# NewWiring.net
KiCad netlist of a schematic drawn in EAGLE
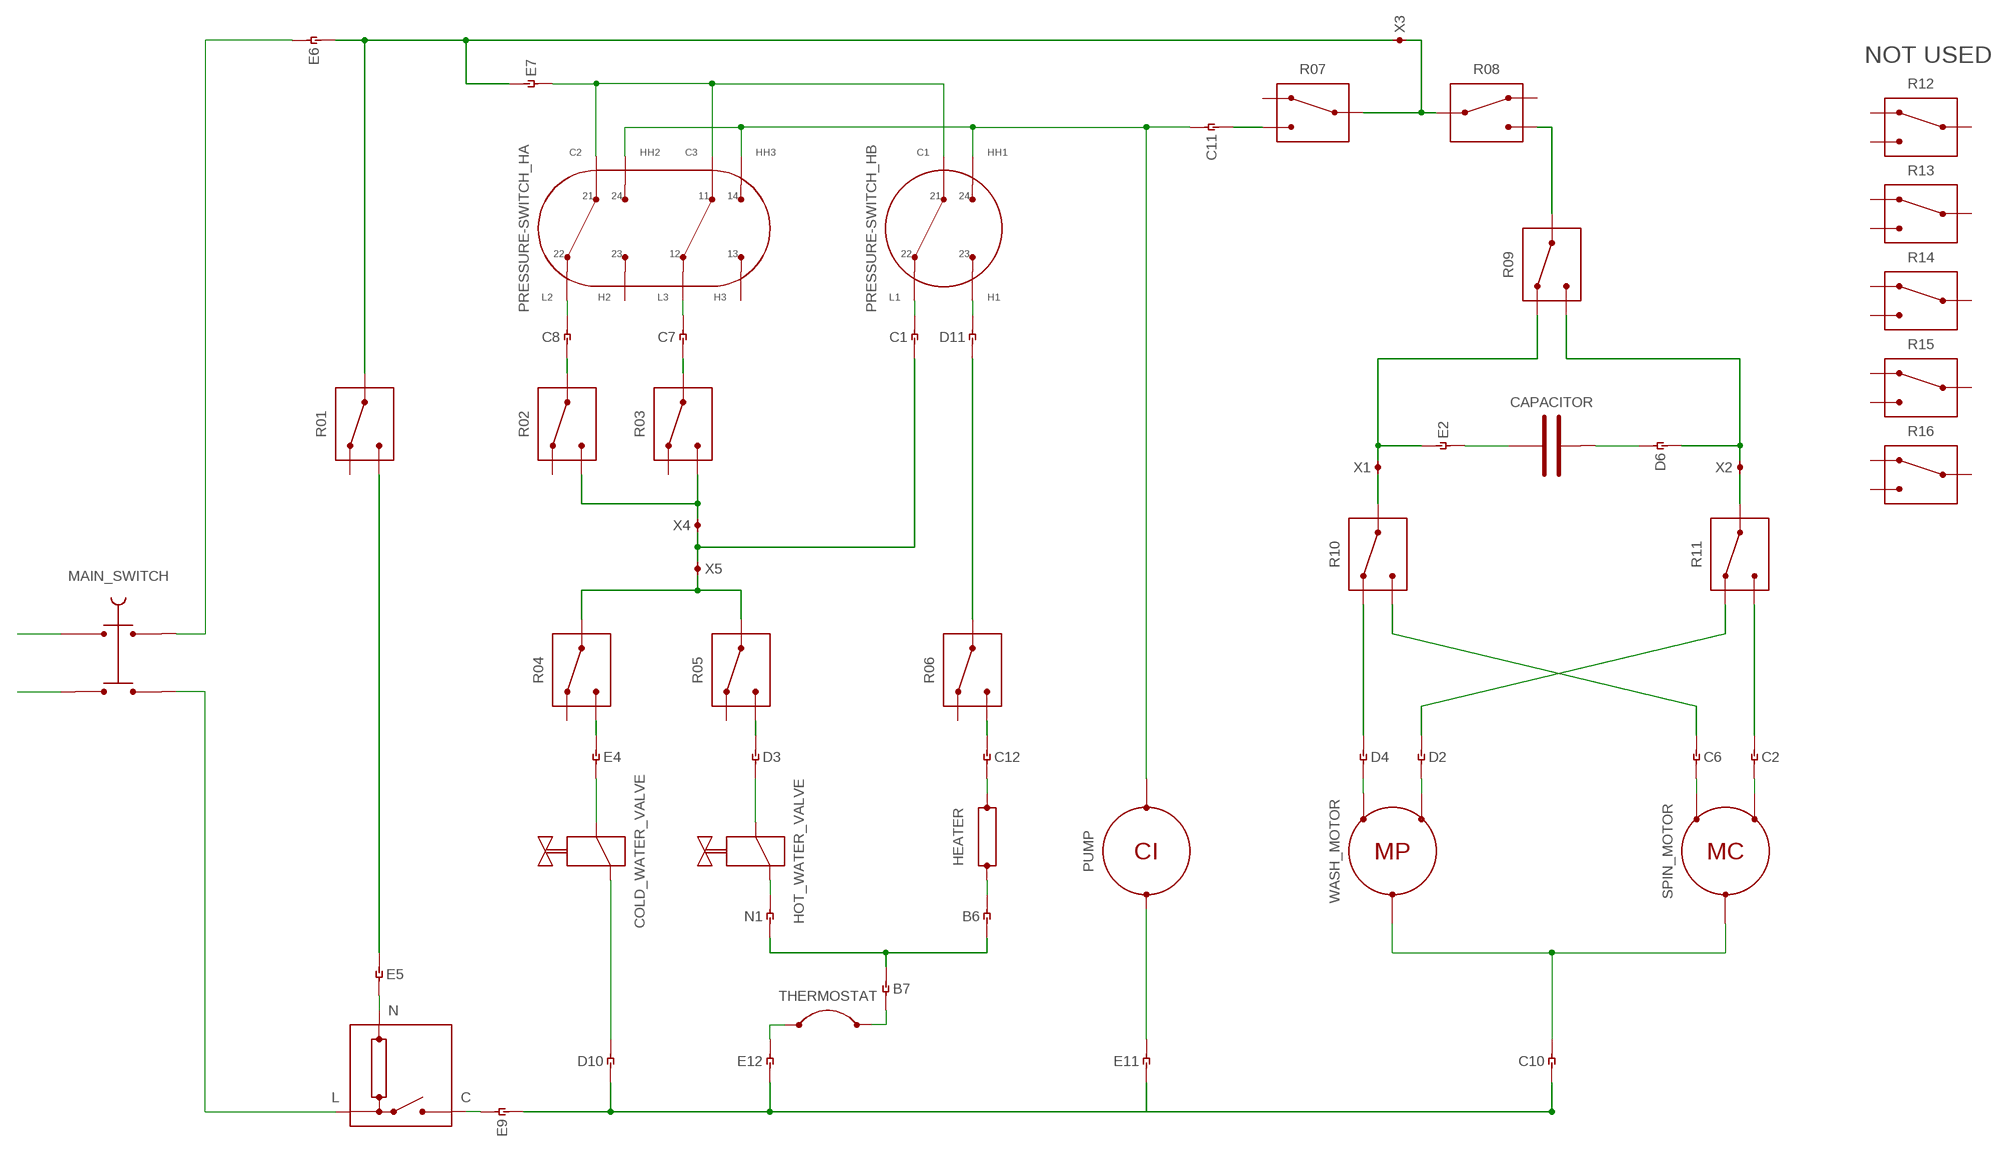
[diagram p0: schematic, sheet 1]

(export (version "E")
  (design (tool "Eeschema 10.0.6"))
  (components
    (comp (ref "B6")
      (value "CABLE")
      (footprint "eagle-import:CABLE")
      (libsource (lib "eagle-import") (part "CABLE"))
    )
    (comp (ref "B7")
      (value "CABLE")
      (footprint "eagle-import:CABLE")
      (libsource (lib "eagle-import") (part "CABLE"))
    )
    (comp (ref "C1")
      (value "CABLE")
      (footprint "eagle-import:CABLE")
      (libsource (lib "eagle-import") (part "CABLE"))
    )
    (comp (ref "C2")
      (value "CABLE")
      (footprint "eagle-import:CABLE")
      (libsource (lib "eagle-import") (part "CABLE"))
    )
    (comp (ref "C6")
      (value "CABLE")
      (footprint "eagle-import:CABLE")
      (libsource (lib "eagle-import") (part "CABLE"))
    )
    (comp (ref "C7")
      (value "CABLE")
      (footprint "eagle-import:CABLE")
      (libsource (lib "eagle-import") (part "CABLE"))
    )
    (comp (ref "C8")
      (value "CABLE")
      (footprint "eagle-import:CABLE")
      (libsource (lib "eagle-import") (part "CABLE"))
    )
    (comp (ref "C10")
      (value "CABLE")
      (footprint "eagle-import:CABLE")
      (libsource (lib "eagle-import") (part "CABLE"))
    )
    (comp (ref "C11")
      (value "CABLE")
      (footprint "eagle-import:CABLE")
      (libsource (lib "eagle-import") (part "CABLE"))
    )
    (comp (ref "C12")
      (value "CABLE")
      (footprint "eagle-import:CABLE")
      (libsource (lib "eagle-import") (part "CABLE"))
    )
    (comp (ref "CAPACITOR")
      (value "CAPACITOR")
      (footprint "eagle-import:CAPACITOR")
      (libsource (lib "eagle-import") (part "CAPACITOR"))
    )
    (comp (ref "COLD_WATER_VALVE")
      (value "VALVE")
      (footprint "eagle-import:VALVE")
      (libsource (lib "eagle-import") (part "VALVE"))
    )
    (comp (ref "D2")
      (value "CABLE")
      (footprint "eagle-import:CABLE")
      (libsource (lib "eagle-import") (part "CABLE"))
    )
    (comp (ref "D3")
      (value "CABLE")
      (footprint "eagle-import:CABLE")
      (libsource (lib "eagle-import") (part "CABLE"))
    )
    (comp (ref "D4")
      (value "CABLE")
      (footprint "eagle-import:CABLE")
      (libsource (lib "eagle-import") (part "CABLE"))
    )
    (comp (ref "D6")
      (value "CABLE")
      (footprint "eagle-import:CABLE")
      (libsource (lib "eagle-import") (part "CABLE"))
    )
    (comp (ref "D10")
      (value "CABLE")
      (footprint "eagle-import:CABLE")
      (libsource (lib "eagle-import") (part "CABLE"))
    )
    (comp (ref "D11")
      (value "CABLE")
      (footprint "eagle-import:CABLE")
      (libsource (lib "eagle-import") (part "CABLE"))
    )
    (comp (ref "E2")
      (value "CABLE")
      (footprint "eagle-import:CABLE")
      (libsource (lib "eagle-import") (part "CABLE"))
    )
    (comp (ref "E4")
      (value "CABLE")
      (footprint "eagle-import:CABLE")
      (libsource (lib "eagle-import") (part "CABLE"))
    )
    (comp (ref "E5")
      (value "CABLE")
      (footprint "eagle-import:CABLE")
      (libsource (lib "eagle-import") (part "CABLE"))
    )
    (comp (ref "E6")
      (value "CABLE")
      (footprint "eagle-import:CABLE")
      (libsource (lib "eagle-import") (part "CABLE"))
    )
    (comp (ref "E7")
      (value "CABLE")
      (footprint "eagle-import:CABLE")
      (libsource (lib "eagle-import") (part "CABLE"))
    )
    (comp (ref "E9")
      (value "CABLE")
      (footprint "eagle-import:CABLE")
      (libsource (lib "eagle-import") (part "CABLE"))
    )
    (comp (ref "E11")
      (value "CABLE")
      (footprint "eagle-import:CABLE")
      (libsource (lib "eagle-import") (part "CABLE"))
    )
    (comp (ref "E12")
      (value "CABLE")
      (footprint "eagle-import:CABLE")
      (libsource (lib "eagle-import") (part "CABLE"))
    )
    (comp (ref "HEATER")
      (value "HEATER")
      (footprint "eagle-import:HEATER")
      (libsource (lib "eagle-import") (part "HEATER"))
    )
    (comp (ref "HOT_WATER_VALVE")
      (value "VALVE")
      (footprint "eagle-import:VALVE")
      (libsource (lib "eagle-import") (part "VALVE"))
    )
    (comp (ref "MAIN_SWITCH")
      (value "SWITCH")
      (footprint "eagle-import:SWITCH")
      (libsource (lib "eagle-import") (part "SWITCH"))
    )
    (comp (ref "N1")
      (value "CABLE")
      (footprint "eagle-import:CABLE")
      (libsource (lib "eagle-import") (part "CABLE"))
    )
    (comp (ref "PRESSURE-SWITCH_HA")
      (value "PS2")
      (footprint "eagle-import:PS2")
      (libsource (lib "eagle-import") (part "PS2"))
    )
    (comp (ref "PRESSURE-SWITCH_HB")
      (value "PS1")
      (footprint "eagle-import:PS1")
      (libsource (lib "eagle-import") (part "PS1"))
    )
    (comp (ref "PUMP")
      (value "CI")
      (footprint "eagle-import:MOTOR-2")
      (libsource (lib "eagle-import") (part "MOTOR-2"))
    )
    (comp (ref "R01")
      (value "RELAY")
      (footprint "eagle-import:RELAY")
      (libsource (lib "eagle-import") (part "RELAY"))
    )
    (comp (ref "R02")
      (value "RELAY")
      (footprint "eagle-import:RELAY")
      (libsource (lib "eagle-import") (part "RELAY"))
    )
    (comp (ref "R03")
      (value "RELAY")
      (footprint "eagle-import:RELAY")
      (libsource (lib "eagle-import") (part "RELAY"))
    )
    (comp (ref "R04")
      (value "RELAY")
      (footprint "eagle-import:RELAY")
      (libsource (lib "eagle-import") (part "RELAY"))
    )
    (comp (ref "R05")
      (value "RELAY")
      (footprint "eagle-import:RELAY")
      (libsource (lib "eagle-import") (part "RELAY"))
    )
    (comp (ref "R06")
      (value "RELAY")
      (footprint "eagle-import:RELAY")
      (libsource (lib "eagle-import") (part "RELAY"))
    )
    (comp (ref "R07")
      (value "RELAY")
      (footprint "eagle-import:RELAY")
      (libsource (lib "eagle-import") (part "RELAY"))
    )
    (comp (ref "R08")
      (value "RELAY")
      (footprint "eagle-import:RELAY")
      (libsource (lib "eagle-import") (part "RELAY"))
    )
    (comp (ref "R09")
      (value "RELAY")
      (footprint "eagle-import:RELAY")
      (libsource (lib "eagle-import") (part "RELAY"))
    )
    (comp (ref "R10")
      (value "RELAY")
      (footprint "eagle-import:RELAY")
      (libsource (lib "eagle-import") (part "RELAY"))
    )
    (comp (ref "R11")
      (value "RELAY")
      (footprint "eagle-import:RELAY")
      (libsource (lib "eagle-import") (part "RELAY"))
    )
    (comp (ref "R12")
      (value "RELAY")
      (footprint "eagle-import:RELAY")
      (libsource (lib "eagle-import") (part "RELAY"))
    )
    (comp (ref "R13")
      (value "RELAY")
      (footprint "eagle-import:RELAY")
      (libsource (lib "eagle-import") (part "RELAY"))
    )
    (comp (ref "R14")
      (value "RELAY")
      (footprint "eagle-import:RELAY")
      (libsource (lib "eagle-import") (part "RELAY"))
    )
    (comp (ref "R15")
      (value "RELAY")
      (footprint "eagle-import:RELAY")
      (libsource (lib "eagle-import") (part "RELAY"))
    )
    (comp (ref "R16")
      (value "RELAY")
      (footprint "eagle-import:RELAY")
      (libsource (lib "eagle-import") (part "RELAY"))
    )
    (comp (ref "SPIN_MOTOR")
      (value "MC")
      (footprint "eagle-import:MOTOR-3")
      (libsource (lib "eagle-import") (part "MOTOR-3"))
    )
    (comp (ref "THERMOSTAT")
      (value "THERMOSTAT")
      (footprint "eagle-import:THERMOSTAT")
      (libsource (lib "eagle-import") (part "THERMOSTAT"))
    )
    (comp (ref "U$1")
      (value "LOCK")
      (footprint "eagle-import:LOCK")
      (libsource (lib "eagle-import") (part "LOCK"))
    )
    (comp (ref "WASH_MOTOR")
      (value "MP")
      (footprint "eagle-import:MOTOR-3")
      (libsource (lib "eagle-import") (part "MOTOR-3"))
    )
    (comp (ref "X1")
      (value "DOMINO")
      (footprint "eagle-import:DOMINO")
      (libsource (lib "eagle-import") (part "DOMINO"))
    )
    (comp (ref "X2")
      (value "DOMINO")
      (footprint "eagle-import:DOMINO")
      (libsource (lib "eagle-import") (part "DOMINO"))
    )
    (comp (ref "X3")
      (value "DOMINO")
      (footprint "eagle-import:DOMINO")
      (libsource (lib "eagle-import") (part "DOMINO"))
    )
    (comp (ref "X4")
      (value "DOMINO")
      (footprint "eagle-import:DOMINO")
      (libsource (lib "eagle-import") (part "DOMINO"))
    )
    (comp (ref "X5")
      (value "DOMINO")
      (footprint "eagle-import:DOMINO")
      (libsource (lib "eagle-import") (part "DOMINO"))
    )
  )
  (nets
    (net (code "1") (name "Net-(B6-PIN1)") (class "Default")
      (node (ref "B6") (pin "P$1") (pinfunction "PIN1_P$1") (pintype "bidirectional"))
      (node (ref "B7") (pin "P$1") (pinfunction "PIN1_P$1") (pintype "bidirectional"))
      (node (ref "N1") (pin "P$1") (pinfunction "PIN1_P$1") (pintype "bidirectional"))
    )
    (net (code "2") (name "Net-(B6-PIN2)") (class "Default")
      (node (ref "B6") (pin "P$2") (pinfunction "PIN2_P$2") (pintype "bidirectional"))
      (node (ref "HEATER") (pin "H1") (pinfunction "P$1_H1") (pintype "bidirectional"))
    )
    (net (code "3") (name "Net-(B7-PIN2)") (class "Default")
      (node (ref "B7") (pin "P$2") (pinfunction "PIN2_P$2") (pintype "bidirectional"))
      (node (ref "THERMOSTAT") (pin "T1") (pinfunction "P$1_T1") (pintype "bidirectional"))
    )
    (net (code "4") (name "Net-(C1-PIN1)") (class "Default")
      (node (ref "C1") (pin "P$1") (pinfunction "PIN1_P$1") (pintype "bidirectional"))
      (node (ref "X4") (pin "P$1") (pinfunction "PIN1_P$1") (pintype "bidirectional"))
      (node (ref "X5") (pin "P$1") (pinfunction "PIN1_P$1") (pintype "bidirectional"))
    )
    (net (code "5") (name "Net-(C1-PIN2)") (class "Default")
      (node (ref "C1") (pin "P$2") (pinfunction "PIN2_P$2") (pintype "bidirectional"))
      (node (ref "PRESSURE-SWITCH_HB") (pin "P$3") (pinfunction "P$3_P$3") (pintype "bidirectional"))
    )
    (net (code "6") (name "Net-(C2-PIN1)") (class "Default")
      (node (ref "C2") (pin "P$1") (pinfunction "PIN1_P$1") (pintype "bidirectional"))
      (node (ref "R11") (pin "T") (pinfunction "T_T") (pintype "bidirectional"))
    )
    (net (code "7") (name "Net-(C2-PIN2)") (class "Default")
      (node (ref "C2") (pin "P$2") (pinfunction "PIN2_P$2") (pintype "bidirectional"))
      (node (ref "SPIN_MOTOR") (pin "M3") (pinfunction "M2_M3") (pintype "bidirectional"))
    )
    (net (code "8") (name "Net-(C6-PIN1)") (class "Default")
      (node (ref "C6") (pin "P$1") (pinfunction "PIN1_P$1") (pintype "bidirectional"))
      (node (ref "R10") (pin "T") (pinfunction "T_T") (pintype "bidirectional"))
    )
    (net (code "9") (name "Net-(C6-PIN2)") (class "Default")
      (node (ref "C6") (pin "P$2") (pinfunction "PIN2_P$2") (pintype "bidirectional"))
      (node (ref "SPIN_MOTOR") (pin "M1") (pinfunction "M1_M1") (pintype "bidirectional"))
    )
    (net (code "10") (name "Net-(C7-PIN1)") (class "Default")
      (node (ref "C7") (pin "P$1") (pinfunction "PIN1_P$1") (pintype "bidirectional"))
      (node (ref "R03") (pin "C") (pinfunction "C_C") (pintype "bidirectional"))
    )
    (net (code "11") (name "Net-(C7-PIN2)") (class "Default")
      (node (ref "C7") (pin "P$2") (pinfunction "PIN2_P$2") (pintype "bidirectional"))
      (node (ref "PRESSURE-SWITCH_HA") (pin "P$6") (pinfunction "P$7_P$6") (pintype "bidirectional"))
    )
    (net (code "12") (name "Net-(C8-PIN1)") (class "Default")
      (node (ref "C8") (pin "P$1") (pinfunction "PIN1_P$1") (pintype "bidirectional"))
      (node (ref "R02") (pin "C") (pinfunction "C_C") (pintype "bidirectional"))
    )
    (net (code "13") (name "Net-(C8-PIN2)") (class "Default")
      (node (ref "C8") (pin "P$2") (pinfunction "PIN2_P$2") (pintype "bidirectional"))
      (node (ref "PRESSURE-SWITCH_HA") (pin "P$2") (pinfunction "P$3_P$2") (pintype "bidirectional"))
    )
    (net (code "14") (name "Net-(C10-PIN1)") (class "Default")
      (node (ref "C10") (pin "P$1") (pinfunction "PIN1_P$1") (pintype "bidirectional"))
      (node (ref "D10") (pin "P$1") (pinfunction "PIN1_P$1") (pintype "bidirectional"))
      (node (ref "E11") (pin "P$1") (pinfunction "PIN1_P$1") (pintype "bidirectional"))
      (node (ref "E12") (pin "P$1") (pinfunction "PIN1_P$1") (pintype "bidirectional"))
      (node (ref "E9") (pin "P$1") (pinfunction "PIN1_P$1") (pintype "bidirectional"))
    )
    (net (code "15") (name "Net-(C10-PIN2)") (class "Default")
      (node (ref "C10") (pin "P$2") (pinfunction "PIN2_P$2") (pintype "bidirectional"))
      (node (ref "SPIN_MOTOR") (pin "MC") (pinfunction "MC_MC") (pintype "bidirectional"))
      (node (ref "WASH_MOTOR") (pin "MC") (pinfunction "MC_MC") (pintype "bidirectional"))
    )
    (net (code "16") (name "Net-(C11-PIN1)") (class "Default")
      (node (ref "C11") (pin "P$1") (pinfunction "PIN1_P$1") (pintype "bidirectional"))
      (node (ref "R07") (pin "T") (pinfunction "T_T") (pintype "bidirectional"))
    )
    (net (code "17") (name "Net-(C11-PIN2)") (class "Default")
      (node (ref "C11") (pin "P$2") (pinfunction "PIN2_P$2") (pintype "bidirectional"))
      (node (ref "PRESSURE-SWITCH_HA") (pin "P$5") (pinfunction "P$6_P$5") (pintype "bidirectional"))
      (node (ref "PRESSURE-SWITCH_HA") (pin "P$8") (pinfunction "P$2_P$8") (pintype "bidirectional"))
      (node (ref "PRESSURE-SWITCH_HB") (pin "P$2") (pinfunction "P$2_P$2") (pintype "bidirectional"))
      (node (ref "PUMP") (pin "M1") (pinfunction "M1_M1") (pintype "bidirectional"))
    )
    (net (code "18") (name "Net-(C12-PIN1)") (class "Default")
      (node (ref "C12") (pin "P$1") (pinfunction "PIN1_P$1") (pintype "bidirectional"))
      (node (ref "R06") (pin "T") (pinfunction "T_T") (pintype "bidirectional"))
    )
    (net (code "19") (name "Net-(C12-PIN2)") (class "Default")
      (node (ref "C12") (pin "P$2") (pinfunction "PIN2_P$2") (pintype "bidirectional"))
      (node (ref "HEATER") (pin "H2") (pinfunction "P$2_H2") (pintype "bidirectional"))
    )
    (net (code "20") (name "Net-(D2-PIN1)") (class "Default")
      (node (ref "D2") (pin "P$1") (pinfunction "PIN1_P$1") (pintype "bidirectional"))
      (node (ref "R11") (pin "R") (pinfunction "R_R") (pintype "bidirectional"))
    )
    (net (code "21") (name "Net-(D2-PIN2)") (class "Default")
      (node (ref "D2") (pin "P$2") (pinfunction "PIN2_P$2") (pintype "bidirectional"))
      (node (ref "WASH_MOTOR") (pin "M3") (pinfunction "M2_M3") (pintype "bidirectional"))
    )
    (net (code "22") (name "Net-(D3-PIN1)") (class "Default")
      (node (ref "D3") (pin "P$1") (pinfunction "PIN1_P$1") (pintype "bidirectional"))
      (node (ref "R05") (pin "T") (pinfunction "T_T") (pintype "bidirectional"))
    )
    (net (code "23") (name "Net-(D3-PIN2)") (class "Default")
      (node (ref "D3") (pin "P$2") (pinfunction "PIN2_P$2") (pintype "bidirectional"))
      (node (ref "HOT_WATER_VALVE") (pin "P$2") (pinfunction "P$2_P$2") (pintype "bidirectional"))
    )
    (net (code "24") (name "Net-(D4-PIN1)") (class "Default")
      (node (ref "D4") (pin "P$1") (pinfunction "PIN1_P$1") (pintype "bidirectional"))
      (node (ref "R10") (pin "R") (pinfunction "R_R") (pintype "bidirectional"))
    )
    (net (code "25") (name "Net-(D4-PIN2)") (class "Default")
      (node (ref "D4") (pin "P$2") (pinfunction "PIN2_P$2") (pintype "bidirectional"))
      (node (ref "WASH_MOTOR") (pin "M1") (pinfunction "M1_M1") (pintype "bidirectional"))
    )
    (net (code "26") (name "Net-(D6-PIN1)") (class "Default")
      (node (ref "D6") (pin "P$1") (pinfunction "PIN1_P$1") (pintype "bidirectional"))
      (node (ref "R09") (pin "T") (pinfunction "T_T") (pintype "bidirectional"))
      (node (ref "X2") (pin "P$2") (pinfunction "PIN2_P$2") (pintype "bidirectional"))
    )
    (net (code "27") (name "Net-(D6-PIN2)") (class "Default")
      (node (ref "CAPACITOR") (pin "C2") (pinfunction "C2_C2") (pintype "bidirectional"))
      (node (ref "D6") (pin "P$2") (pinfunction "PIN2_P$2") (pintype "bidirectional"))
    )
    (net (code "28") (name "Net-(D10-PIN2)") (class "Default")
      (node (ref "COLD_WATER_VALVE") (pin "P$1") (pinfunction "P$1_P$1") (pintype "bidirectional"))
      (node (ref "D10") (pin "P$2") (pinfunction "PIN2_P$2") (pintype "bidirectional"))
    )
    (net (code "29") (name "Net-(D11-PIN1)") (class "Default")
      (node (ref "D11") (pin "P$1") (pinfunction "PIN1_P$1") (pintype "bidirectional"))
      (node (ref "R06") (pin "C") (pinfunction "C_C") (pintype "bidirectional"))
    )
    (net (code "30") (name "Net-(D11-PIN2)") (class "Default")
      (node (ref "D11") (pin "P$2") (pinfunction "PIN2_P$2") (pintype "bidirectional"))
      (node (ref "PRESSURE-SWITCH_HB") (pin "P$4") (pinfunction "P$4_P$4") (pintype "bidirectional"))
    )
    (net (code "31") (name "Net-(E2-PIN1)") (class "Default")
      (node (ref "E2") (pin "P$1") (pinfunction "PIN1_P$1") (pintype "bidirectional"))
      (node (ref "R09") (pin "R") (pinfunction "R_R") (pintype "bidirectional"))
      (node (ref "X1") (pin "P$2") (pinfunction "PIN2_P$2") (pintype "bidirectional"))
    )
    (net (code "32") (name "Net-(E2-PIN2)") (class "Default")
      (node (ref "CAPACITOR") (pin "C1") (pinfunction "C1_C1") (pintype "bidirectional"))
      (node (ref "E2") (pin "P$2") (pinfunction "PIN2_P$2") (pintype "bidirectional"))
    )
    (net (code "33") (name "Net-(E4-PIN1)") (class "Default")
      (node (ref "E4") (pin "P$1") (pinfunction "PIN1_P$1") (pintype "bidirectional"))
      (node (ref "R04") (pin "T") (pinfunction "T_T") (pintype "bidirectional"))
    )
    (net (code "34") (name "Net-(E4-PIN2)") (class "Default")
      (node (ref "COLD_WATER_VALVE") (pin "P$2") (pinfunction "P$2_P$2") (pintype "bidirectional"))
      (node (ref "E4") (pin "P$2") (pinfunction "PIN2_P$2") (pintype "bidirectional"))
    )
    (net (code "35") (name "Net-(E5-PIN1)") (class "Default")
      (node (ref "E5") (pin "P$1") (pinfunction "PIN1_P$1") (pintype "bidirectional"))
      (node (ref "R01") (pin "T") (pinfunction "T_T") (pintype "bidirectional"))
    )
    (net (code "36") (name "Net-(E5-PIN2)") (class "Default")
      (node (ref "E5") (pin "P$2") (pinfunction "PIN2_P$2") (pintype "bidirectional"))
      (node (ref "U$1") (pin "N") (pinfunction "N_N") (pintype "bidirectional"))
    )
    (net (code "37") (name "Net-(E6-PIN1)") (class "Default")
      (node (ref "E6") (pin "P$1") (pinfunction "PIN1_P$1") (pintype "bidirectional"))
      (node (ref "E7") (pin "P$1") (pinfunction "PIN1_P$1") (pintype "bidirectional"))
      (node (ref "R01") (pin "C") (pinfunction "C_C") (pintype "bidirectional"))
      (node (ref "X3") (pin "P$1") (pinfunction "PIN1_P$1") (pintype "bidirectional"))
    )
    (net (code "38") (name "Net-(E6-PIN2)") (class "Default")
      (node (ref "E6") (pin "P$2") (pinfunction "PIN2_P$2") (pintype "bidirectional"))
      (node (ref "MAIN_SWITCH") (pin "O1") (pinfunction "OUT1_O1") (pintype "bidirectional"))
    )
    (net (code "39") (name "Net-(E7-PIN2)") (class "Default")
      (node (ref "E7") (pin "P$2") (pinfunction "PIN2_P$2") (pintype "bidirectional"))
      (node (ref "PRESSURE-SWITCH_HA") (pin "P$1") (pinfunction "P$1_P$1") (pintype "bidirectional"))
      (node (ref "PRESSURE-SWITCH_HA") (pin "P$4") (pinfunction "P$5_P$4") (pintype "bidirectional"))
      (node (ref "PRESSURE-SWITCH_HB") (pin "P$1") (pinfunction "P$1_P$1") (pintype "bidirectional"))
    )
    (net (code "40") (name "Net-(E9-PIN2)") (class "Default")
      (node (ref "E9") (pin "P$2") (pinfunction "PIN2_P$2") (pintype "bidirectional"))
      (node (ref "U$1") (pin "C") (pinfunction "C_C") (pintype "bidirectional"))
    )
    (net (code "41") (name "Net-(E11-PIN2)") (class "Default")
      (node (ref "E11") (pin "P$2") (pinfunction "PIN2_P$2") (pintype "bidirectional"))
      (node (ref "PUMP") (pin "M3") (pinfunction "M2_M3") (pintype "bidirectional"))
    )
    (net (code "42") (name "Net-(E12-PIN2)") (class "Default")
      (node (ref "E12") (pin "P$2") (pinfunction "PIN2_P$2") (pintype "bidirectional"))
      (node (ref "THERMOSTAT") (pin "T2") (pinfunction "P$2_T2") (pintype "bidirectional"))
    )
    (net (code "43") (name "Net-(MAIN_SWITCH-OUT2)") (class "Default")
      (node (ref "MAIN_SWITCH") (pin "O2") (pinfunction "OUT2_O2") (pintype "bidirectional"))
      (node (ref "U$1") (pin "L") (pinfunction "L_L") (pintype "bidirectional"))
    )
    (net (code "44") (name "Net-(N1-PIN2)") (class "Default")
      (node (ref "HOT_WATER_VALVE") (pin "P$1") (pinfunction "P$1_P$1") (pintype "bidirectional"))
      (node (ref "N1") (pin "P$2") (pinfunction "PIN2_P$2") (pintype "bidirectional"))
    )
    (net (code "45") (name "Net-(R08-PadT)") (class "Default")
      (node (ref "R08") (pin "T") (pinfunction "T_T") (pintype "bidirectional"))
      (node (ref "R09") (pin "C") (pinfunction "C_C") (pintype "bidirectional"))
    )
    (net (code "46") (name "Net-(X1-PIN1)") (class "Default")
      (node (ref "R10") (pin "C") (pinfunction "C_C") (pintype "bidirectional"))
      (node (ref "X1") (pin "P$1") (pinfunction "PIN1_P$1") (pintype "bidirectional"))
    )
    (net (code "47") (name "Net-(X2-PIN1)") (class "Default")
      (node (ref "R11") (pin "C") (pinfunction "C_C") (pintype "bidirectional"))
      (node (ref "X2") (pin "P$1") (pinfunction "PIN1_P$1") (pintype "bidirectional"))
    )
    (net (code "48") (name "Net-(X3-PIN2)") (class "Default")
      (node (ref "R07") (pin "C") (pinfunction "C_C") (pintype "bidirectional"))
      (node (ref "R08") (pin "C") (pinfunction "C_C") (pintype "bidirectional"))
      (node (ref "X3") (pin "P$2") (pinfunction "PIN2_P$2") (pintype "bidirectional"))
    )
    (net (code "49") (name "Net-(X4-PIN2)") (class "Default")
      (node (ref "R02") (pin "T") (pinfunction "T_T") (pintype "bidirectional"))
      (node (ref "R03") (pin "T") (pinfunction "T_T") (pintype "bidirectional"))
      (node (ref "X4") (pin "P$2") (pinfunction "PIN2_P$2") (pintype "bidirectional"))
    )
    (net (code "50") (name "Net-(X5-PIN2)") (class "Default")
      (node (ref "R04") (pin "C") (pinfunction "C_C") (pintype "bidirectional"))
      (node (ref "R05") (pin "C") (pinfunction "C_C") (pintype "bidirectional"))
      (node (ref "X5") (pin "P$2") (pinfunction "PIN2_P$2") (pintype "bidirectional"))
    )
    (net (code "51") (name "unconnected-(MAIN_SWITCH-IN1-PadI1)") (class "Default")
      (node (ref "MAIN_SWITCH") (pin "I1") (pinfunction "IN1_I1") (pintype "bidirectional"))
    )
    (net (code "52") (name "unconnected-(MAIN_SWITCH-IN2-PadI2)") (class "Default")
      (node (ref "MAIN_SWITCH") (pin "I2") (pinfunction "IN2_I2") (pintype "bidirectional"))
    )
    (net (code "53") (name "unconnected-(PRESSURE-SWITCH_HA-P$4-PadP$3)") (class "Default")
      (node (ref "PRESSURE-SWITCH_HA") (pin "P$3") (pinfunction "P$4_P$3") (pintype "bidirectional"))
    )
    (net (code "54") (name "unconnected-(PRESSURE-SWITCH_HA-P$8-PadP$7)") (class "Default")
      (node (ref "PRESSURE-SWITCH_HA") (pin "P$7") (pinfunction "P$8_P$7") (pintype "bidirectional"))
    )
    (net (code "55") (name "unconnected-(R01-PadR)") (class "Default")
      (node (ref "R01") (pin "R") (pinfunction "R_R") (pintype "bidirectional"))
    )
    (net (code "56") (name "unconnected-(R02-PadR)") (class "Default")
      (node (ref "R02") (pin "R") (pinfunction "R_R") (pintype "bidirectional"))
    )
    (net (code "57") (name "unconnected-(R03-PadR)") (class "Default")
      (node (ref "R03") (pin "R") (pinfunction "R_R") (pintype "bidirectional"))
    )
    (net (code "58") (name "unconnected-(R04-PadR)") (class "Default")
      (node (ref "R04") (pin "R") (pinfunction "R_R") (pintype "bidirectional"))
    )
    (net (code "59") (name "unconnected-(R05-PadR)") (class "Default")
      (node (ref "R05") (pin "R") (pinfunction "R_R") (pintype "bidirectional"))
    )
    (net (code "60") (name "unconnected-(R06-PadR)") (class "Default")
      (node (ref "R06") (pin "R") (pinfunction "R_R") (pintype "bidirectional"))
    )
    (net (code "61") (name "unconnected-(R07-PadR)") (class "Default")
      (node (ref "R07") (pin "R") (pinfunction "R_R") (pintype "bidirectional"))
    )
    (net (code "62") (name "unconnected-(R08-PadR)") (class "Default")
      (node (ref "R08") (pin "R") (pinfunction "R_R") (pintype "bidirectional"))
    )
    (net (code "63") (name "unconnected-(R12-PadC)") (class "Default")
      (node (ref "R12") (pin "C") (pinfunction "C_C") (pintype "bidirectional"))
    )
    (net (code "64") (name "unconnected-(R12-PadR)") (class "Default")
      (node (ref "R12") (pin "R") (pinfunction "R_R") (pintype "bidirectional"))
    )
    (net (code "65") (name "unconnected-(R12-PadT)") (class "Default")
      (node (ref "R12") (pin "T") (pinfunction "T_T") (pintype "bidirectional"))
    )
    (net (code "66") (name "unconnected-(R13-PadC)") (class "Default")
      (node (ref "R13") (pin "C") (pinfunction "C_C") (pintype "bidirectional"))
    )
    (net (code "67") (name "unconnected-(R13-PadR)") (class "Default")
      (node (ref "R13") (pin "R") (pinfunction "R_R") (pintype "bidirectional"))
    )
    (net (code "68") (name "unconnected-(R13-PadT)") (class "Default")
      (node (ref "R13") (pin "T") (pinfunction "T_T") (pintype "bidirectional"))
    )
    (net (code "69") (name "unconnected-(R14-PadC)") (class "Default")
      (node (ref "R14") (pin "C") (pinfunction "C_C") (pintype "bidirectional"))
    )
    (net (code "70") (name "unconnected-(R14-PadR)") (class "Default")
      (node (ref "R14") (pin "R") (pinfunction "R_R") (pintype "bidirectional"))
    )
    (net (code "71") (name "unconnected-(R14-PadT)") (class "Default")
      (node (ref "R14") (pin "T") (pinfunction "T_T") (pintype "bidirectional"))
    )
    (net (code "72") (name "unconnected-(R15-PadC)") (class "Default")
      (node (ref "R15") (pin "C") (pinfunction "C_C") (pintype "bidirectional"))
    )
    (net (code "73") (name "unconnected-(R15-PadR)") (class "Default")
      (node (ref "R15") (pin "R") (pinfunction "R_R") (pintype "bidirectional"))
    )
    (net (code "74") (name "unconnected-(R15-PadT)") (class "Default")
      (node (ref "R15") (pin "T") (pinfunction "T_T") (pintype "bidirectional"))
    )
    (net (code "75") (name "unconnected-(R16-PadC)") (class "Default")
      (node (ref "R16") (pin "C") (pinfunction "C_C") (pintype "bidirectional"))
    )
    (net (code "76") (name "unconnected-(R16-PadR)") (class "Default")
      (node (ref "R16") (pin "R") (pinfunction "R_R") (pintype "bidirectional"))
    )
    (net (code "77") (name "unconnected-(R16-PadT)") (class "Default")
      (node (ref "R16") (pin "T") (pinfunction "T_T") (pintype "bidirectional"))
    )
  )
)
